# 4HP_555_eg.net
KiCad netlist of a schematic drawn in EAGLE
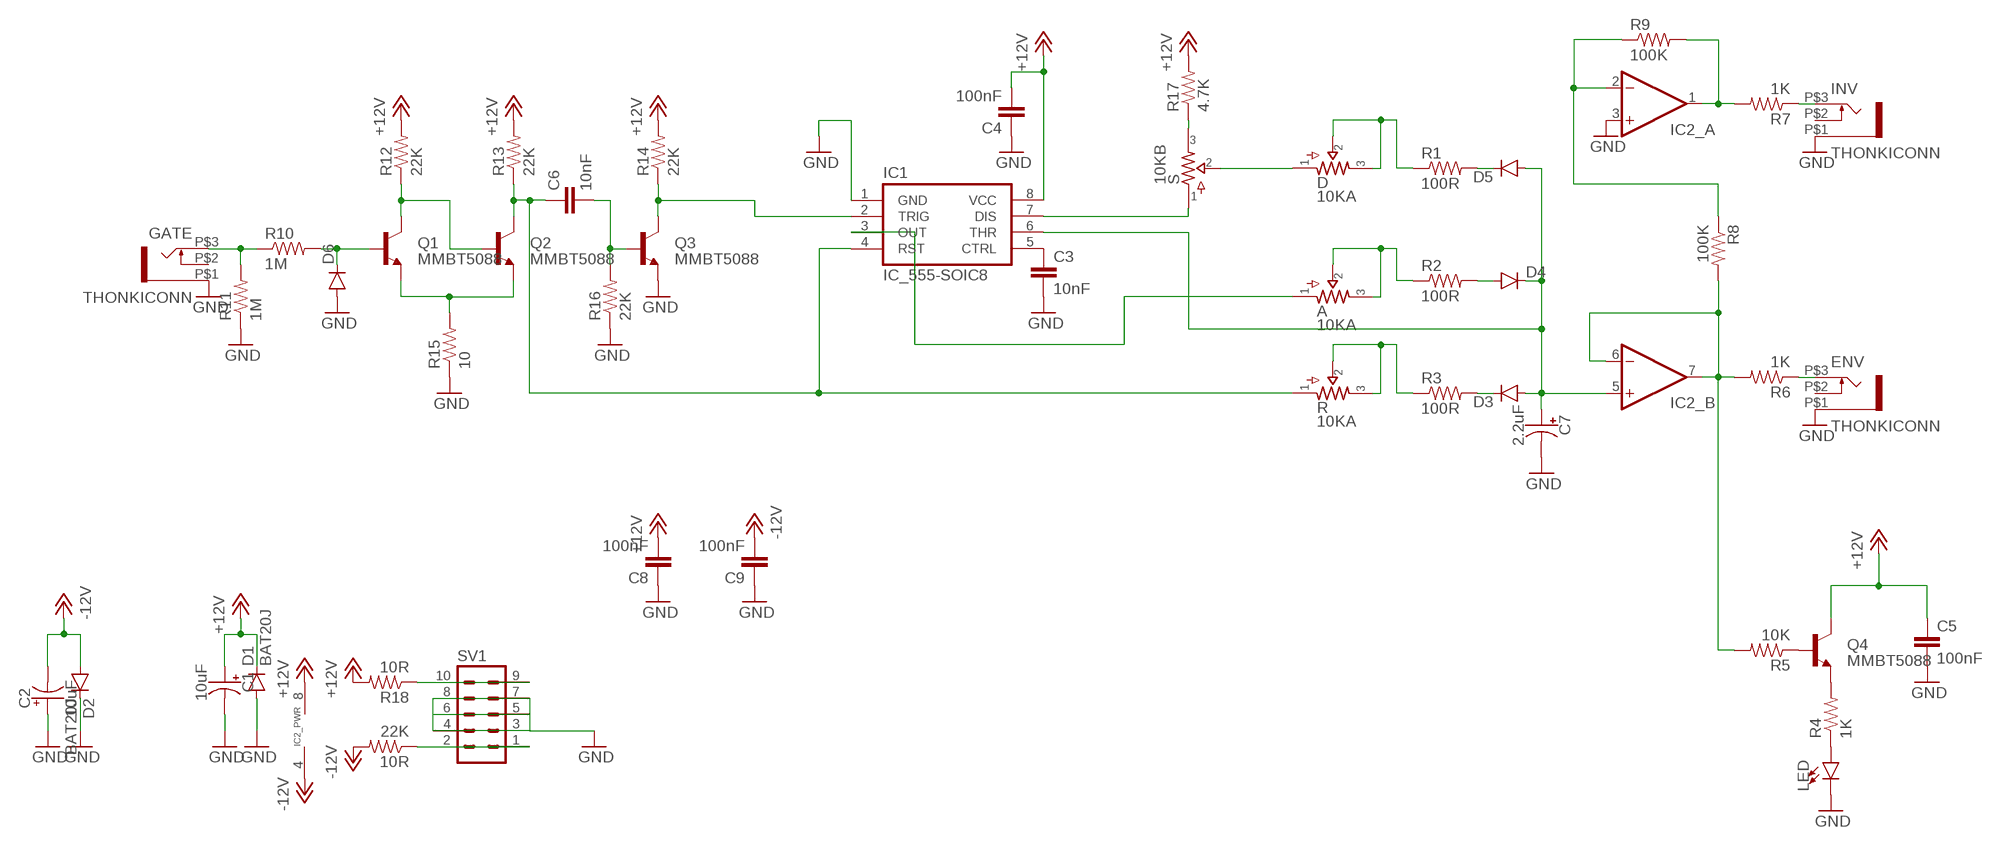
[diagram p0: schematic, sheet 1]

(export (version "E")
  (design (tool "Eeschema 10.0.6"))
  (components
    (comp (ref "10R")
      (value "22K")
      (footprint "eagle-import:0603-RES")
      (libsource (lib "eagle-import") (part "RESISTOR0603-RES"))
    )
    (comp (ref "A")
      (value "10KA")
      (footprint "eagle-import:9MM_W_MOUNTS-2MMHOLES")
      (libsource (lib "eagle-import") (part "POTS9MM_MOUNTED_2MMH"))
    )
    (comp (ref "C1")
      (value "10uF")
      (footprint "eagle-import:050_020_1")
      (libsource (lib "eagle-import") (part "0501"))
    )
    (comp (ref "C2")
      (value "10uF")
      (footprint "eagle-import:050_020_1")
      (libsource (lib "eagle-import") (part "0501"))
    )
    (comp (ref "C3")
      (value "10nF")
      (footprint "eagle-import:0603-CAP")
      (libsource (lib "eagle-import") (part "CAP0603-CAP"))
    )
    (comp (ref "C4")
      (value "100nF")
      (footprint "eagle-import:0603-CAP")
      (libsource (lib "eagle-import") (part "CAP0603-CAP"))
    )
    (comp (ref "C5")
      (value "100nF")
      (footprint "eagle-import:0603-CAP")
      (libsource (lib "eagle-import") (part "CAP0603-CAP"))
    )
    (comp (ref "C6")
      (value "10nF")
      (footprint "eagle-import:0603-CAP")
      (libsource (lib "eagle-import") (part "CAP0603-CAP"))
    )
    (comp (ref "C7")
      (value "2.2uF")
      (footprint "eagle-import:050_020_1")
      (libsource (lib "eagle-import") (part "0501"))
    )
    (comp (ref "C8")
      (value "100nF")
      (footprint "eagle-import:0603-CAP")
      (libsource (lib "eagle-import") (part "CAP0603-CAP"))
    )
    (comp (ref "C9")
      (value "100nF")
      (footprint "eagle-import:0603-CAP")
      (libsource (lib "eagle-import") (part "CAP0603-CAP"))
    )
    (comp (ref "D")
      (value "10KA")
      (footprint "eagle-import:9MM_W_MOUNTS-2MMHOLES")
      (libsource (lib "eagle-import") (part "POTS9MM_MOUNTED_2MMH"))
    )
    (comp (ref "D1")
      (value "BAT20J")
      (footprint "eagle-import:SOD-123")
      (libsource (lib "eagle-import") (part "DIODESOD123"))
    )
    (comp (ref "D2")
      (value "BAT20J")
      (footprint "eagle-import:SOD-123")
      (libsource (lib "eagle-import") (part "DIODESOD123"))
    )
    (comp (ref "D3")
      (value "DIODESOD")
      (footprint "eagle-import:SOD-323")
      (libsource (lib "eagle-import") (part "DIODESOD"))
    )
    (comp (ref "D4")
      (value "DIODESOD")
      (footprint "eagle-import:SOD-323")
      (libsource (lib "eagle-import") (part "DIODESOD"))
    )
    (comp (ref "D5")
      (value "DIODESOD")
      (footprint "eagle-import:SOD-323")
      (libsource (lib "eagle-import") (part "DIODESOD"))
    )
    (comp (ref "D6")
      (value "DIODESOD")
      (footprint "eagle-import:SOD-323")
      (libsource (lib "eagle-import") (part "DIODESOD"))
    )
    (comp (ref "ENV")
      (value "THONKICONN")
      (footprint "eagle-import:THONKICONN")
      (libsource (lib "eagle-import") (part "THONKICONN"))
    )
    (comp (ref "GATE")
      (value "THONKICONN")
      (footprint "eagle-import:THONKICONN")
      (libsource (lib "eagle-import") (part "THONKICONN"))
    )
    (comp (ref "IC1")
      (value "IC_555-SOIC8")
      (footprint "eagle-import:SOIC-8")
      (libsource (lib "eagle-import") (part "IC_555-SOIC8"))
    )
    (comp (ref "IC2")
      (value "DUALSMD")
      (footprint "eagle-import:SO08")
      (libsource (lib "eagle-import") (part "DUALSMD"))
    )
    (comp (ref "INV")
      (value "THONKICONN")
      (footprint "eagle-import:THONKICONN")
      (libsource (lib "eagle-import") (part "THONKICONN"))
    )
    (comp (ref "LED")
      (value "LED5MM")
      (footprint "eagle-import:LED_5MM")
      (libsource (lib "eagle-import") (part "LED5MM"))
    )
    (comp (ref "Q1")
      (value "MMBT5088")
      (footprint "eagle-import:SOT23")
      (libsource (lib "eagle-import") (part "TRANSISTOR_NPNMMBT5088"))
    )
    (comp (ref "Q2")
      (value "MMBT5088")
      (footprint "eagle-import:SOT23")
      (libsource (lib "eagle-import") (part "TRANSISTOR_NPNMMBT5088"))
    )
    (comp (ref "Q3")
      (value "MMBT5088")
      (footprint "eagle-import:SOT23")
      (libsource (lib "eagle-import") (part "TRANSISTOR_NPNMMBT5088"))
    )
    (comp (ref "Q4")
      (value "MMBT5088")
      (footprint "eagle-import:SOT23")
      (libsource (lib "eagle-import") (part "TRANSISTOR_NPNMMBT5088"))
    )
    (comp (ref "R")
      (value "10KA")
      (footprint "eagle-import:9MM_W_MOUNTS-2MMHOLES")
      (libsource (lib "eagle-import") (part "POTS9MM_MOUNTED_2MMH"))
    )
    (comp (ref "R1")
      (value "100R")
      (footprint "eagle-import:0603-RES")
      (libsource (lib "eagle-import") (part "RESISTOR0603-RES"))
    )
    (comp (ref "R2")
      (value "100R")
      (footprint "eagle-import:0603-RES")
      (libsource (lib "eagle-import") (part "RESISTOR0603-RES"))
    )
    (comp (ref "R3")
      (value "100R")
      (footprint "eagle-import:0603-RES")
      (libsource (lib "eagle-import") (part "RESISTOR0603-RES"))
    )
    (comp (ref "R4")
      (value "1K")
      (footprint "eagle-import:0603-RES")
      (libsource (lib "eagle-import") (part "RESISTOR0603-RES"))
    )
    (comp (ref "R5")
      (value "10K")
      (footprint "eagle-import:0603-RES")
      (libsource (lib "eagle-import") (part "RESISTOR0603-RES"))
    )
    (comp (ref "R6")
      (value "1K")
      (footprint "eagle-import:0603-RES")
      (libsource (lib "eagle-import") (part "RESISTOR0603-RES"))
    )
    (comp (ref "R7")
      (value "1K")
      (footprint "eagle-import:0603-RES")
      (libsource (lib "eagle-import") (part "RESISTOR0603-RES"))
    )
    (comp (ref "R8")
      (value "100K")
      (footprint "eagle-import:0603-RES")
      (libsource (lib "eagle-import") (part "RESISTOR0603-RES"))
    )
    (comp (ref "R9")
      (value "100K")
      (footprint "eagle-import:0603-RES")
      (libsource (lib "eagle-import") (part "RESISTOR0603-RES"))
    )
    (comp (ref "R10")
      (value "1M")
      (footprint "eagle-import:0603-RES")
      (libsource (lib "eagle-import") (part "RESISTOR0603-RES"))
    )
    (comp (ref "R11")
      (value "1M")
      (footprint "eagle-import:0603-RES")
      (libsource (lib "eagle-import") (part "RESISTOR0603-RES"))
    )
    (comp (ref "R12")
      (value "22K")
      (footprint "eagle-import:0603-RES")
      (libsource (lib "eagle-import") (part "RESISTOR0603-RES"))
    )
    (comp (ref "R13")
      (value "22K")
      (footprint "eagle-import:0603-RES")
      (libsource (lib "eagle-import") (part "RESISTOR0603-RES"))
    )
    (comp (ref "R14")
      (value "22K")
      (footprint "eagle-import:0603-RES")
      (libsource (lib "eagle-import") (part "RESISTOR0603-RES"))
    )
    (comp (ref "R15")
      (value "10")
      (footprint "eagle-import:0603-RES")
      (libsource (lib "eagle-import") (part "RESISTOR0603-RES"))
    )
    (comp (ref "R16")
      (value "22K")
      (footprint "eagle-import:0603-RES")
      (libsource (lib "eagle-import") (part "RESISTOR0603-RES"))
    )
    (comp (ref "R17")
      (value "4.7K")
      (footprint "eagle-import:0603-RES")
      (libsource (lib "eagle-import") (part "RESISTOR0603-RES"))
    )
    (comp (ref "R18")
      (value "10R")
      (footprint "eagle-import:0603-RES")
      (libsource (lib "eagle-import") (part "RESISTOR0603-RES"))
    )
    (comp (ref "S")
      (value "10KB")
      (footprint "eagle-import:9MM_W_MOUNTS-2MMHOLES")
      (libsource (lib "eagle-import") (part "POTS9MM_MOUNTED_2MMH"))
    )
    (comp (ref "SV1")
      (value "EURO_POWER_HEADER")
      (footprint "eagle-import:EURO_POWER_HEADER")
      (libsource (lib "eagle-import") (part "EURO_POWER_HEADER"))
    )
  )
  (nets
    (net (code "1") (name "+12V") (class "Default")
      (node (ref "C1") (pin "+") (pinfunction "+_+") (pintype "passive"))
      (node (ref "C4") (pin "2") (pinfunction "2_2") (pintype "passive"))
      (node (ref "C5") (pin "1") (pinfunction "1_1") (pintype "passive"))
      (node (ref "C8") (pin "2") (pinfunction "2_2") (pintype "passive"))
      (node (ref "D1") (pin "C") (pinfunction "C_C") (pintype "passive"))
      (node (ref "IC1") (pin "8") (pinfunction "VCC_8") (pintype "power_in"))
      (node (ref "IC2") (pin "8") (pinfunction "V+_8") (pintype "power_in"))
      (node (ref "Q4") (pin "3") (pinfunction "C_3") (pintype "passive"))
      (node (ref "R12") (pin "2") (pinfunction "2_2") (pintype "passive"))
      (node (ref "R13") (pin "2") (pinfunction "2_2") (pintype "passive"))
      (node (ref "R14") (pin "2") (pinfunction "2_2") (pintype "passive"))
      (node (ref "R17") (pin "2") (pinfunction "2_2") (pintype "passive"))
      (node (ref "R18") (pin "2") (pinfunction "2_2") (pintype "passive"))
    )
    (net (code "2") (name "-12V") (class "Default")
      (node (ref "10R") (pin "2") (pinfunction "2_2") (pintype "passive"))
      (node (ref "C2") (pin "-") (pinfunction "-_-") (pintype "passive"))
      (node (ref "C9") (pin "2") (pinfunction "2_2") (pintype "passive"))
      (node (ref "D2") (pin "A") (pinfunction "A_A") (pintype "passive"))
      (node (ref "IC2") (pin "4") (pinfunction "V-_4") (pintype "power_in"))
    )
    (net (code "3") (name "GND") (class "Default")
      (node (ref "C1") (pin "-") (pinfunction "-_-") (pintype "passive"))
      (node (ref "C2") (pin "+") (pinfunction "+_+") (pintype "passive"))
      (node (ref "C3") (pin "2") (pinfunction "2_2") (pintype "passive"))
      (node (ref "C4") (pin "1") (pinfunction "1_1") (pintype "passive"))
      (node (ref "C5") (pin "2") (pinfunction "2_2") (pintype "passive"))
      (node (ref "C7") (pin "-") (pinfunction "-_-") (pintype "passive"))
      (node (ref "C8") (pin "1") (pinfunction "1_1") (pintype "passive"))
      (node (ref "C9") (pin "1") (pinfunction "1_1") (pintype "passive"))
      (node (ref "D1") (pin "A") (pinfunction "A_A") (pintype "passive"))
      (node (ref "D2") (pin "C") (pinfunction "C_C") (pintype "passive"))
      (node (ref "D6") (pin "A") (pinfunction "A_A") (pintype "passive"))
      (node (ref "ENV") (pin "P$1") (pinfunction "5_P$1") (pintype "passive"))
      (node (ref "GATE") (pin "P$1") (pinfunction "5_P$1") (pintype "passive"))
      (node (ref "IC1") (pin "1") (pinfunction "GND_1") (pintype "power_in"))
      (node (ref "IC2") (pin "3") (pinfunction "+IN_3") (pintype "input"))
      (node (ref "INV") (pin "P$1") (pinfunction "5_P$1") (pintype "passive"))
      (node (ref "LED") (pin "K") (pinfunction "C_K") (pintype "passive"))
      (node (ref "Q3") (pin "2") (pinfunction "E_2") (pintype "passive"))
      (node (ref "R11") (pin "1") (pinfunction "1_1") (pintype "passive"))
      (node (ref "R15") (pin "1") (pinfunction "1_1") (pintype "passive"))
      (node (ref "R16") (pin "1") (pinfunction "1_1") (pintype "passive"))
      (node (ref "SV1") (pin "3") (pinfunction "3_3") (pintype "passive"))
      (node (ref "SV1") (pin "4") (pinfunction "4_4") (pintype "passive"))
      (node (ref "SV1") (pin "5") (pinfunction "5_5") (pintype "passive"))
      (node (ref "SV1") (pin "6") (pinfunction "6_6") (pintype "passive"))
      (node (ref "SV1") (pin "7") (pinfunction "7_7") (pintype "passive"))
      (node (ref "SV1") (pin "8") (pinfunction "8_8") (pintype "passive"))
    )
    (net (code "4") (name "Net-(10R-Pad1)") (class "Default")
      (node (ref "10R") (pin "1") (pinfunction "1_1") (pintype "passive"))
      (node (ref "SV1") (pin "1") (pinfunction "1_1") (pintype "passive"))
      (node (ref "SV1") (pin "2") (pinfunction "2_2") (pintype "passive"))
    )
    (net (code "5") (name "Net-(A-1)") (class "Default")
      (node (ref "A") (pin "P$1") (pinfunction "1_P$1") (pintype "passive"))
      (node (ref "IC1") (pin "3") (pinfunction "OUT_3") (pintype "output"))
    )
    (net (code "6") (name "Net-(A-2)") (class "Default")
      (node (ref "A") (pin "P$2") (pinfunction "2_P$2") (pintype "passive"))
      (node (ref "A") (pin "P$3") (pinfunction "3_P$3") (pintype "passive"))
      (node (ref "R2") (pin "1") (pinfunction "1_1") (pintype "passive"))
    )
    (net (code "7") (name "Net-(D-1)") (class "Default")
      (node (ref "D") (pin "P$1") (pinfunction "1_P$1") (pintype "passive"))
      (node (ref "S") (pin "P$2") (pinfunction "2_P$2") (pintype "passive"))
    )
    (net (code "8") (name "Net-(D-2)") (class "Default")
      (node (ref "D") (pin "P$2") (pinfunction "2_P$2") (pintype "passive"))
      (node (ref "D") (pin "P$3") (pinfunction "3_P$3") (pintype "passive"))
      (node (ref "R1") (pin "1") (pinfunction "1_1") (pintype "passive"))
    )
    (net (code "9") (name "Net-(D3-PadC)") (class "Default")
      (node (ref "D3") (pin "C") (pinfunction "C_C") (pintype "passive"))
      (node (ref "R3") (pin "2") (pinfunction "2_2") (pintype "passive"))
    )
    (net (code "10") (name "Net-(D4-PadA)") (class "Default")
      (node (ref "D4") (pin "A") (pinfunction "A_A") (pintype "passive"))
      (node (ref "R2") (pin "2") (pinfunction "2_2") (pintype "passive"))
    )
    (net (code "11") (name "Net-(D5-PadC)") (class "Default")
      (node (ref "D5") (pin "C") (pinfunction "C_C") (pintype "passive"))
      (node (ref "R1") (pin "2") (pinfunction "2_2") (pintype "passive"))
    )
    (net (code "12") (name "Net-(ENV-3)") (class "Default")
      (node (ref "ENV") (pin "P$3") (pinfunction "3_P$3") (pintype "passive"))
      (node (ref "R6") (pin "1") (pinfunction "1_1") (pintype "passive"))
    )
    (net (code "13") (name "Net-(GATE-3)") (class "Default")
      (node (ref "GATE") (pin "P$3") (pinfunction "3_P$3") (pintype "passive"))
      (node (ref "R10") (pin "1") (pinfunction "1_1") (pintype "passive"))
      (node (ref "R11") (pin "2") (pinfunction "2_2") (pintype "passive"))
    )
    (net (code "14") (name "Net-(IC1-CTRL)") (class "Default")
      (node (ref "C3") (pin "1") (pinfunction "1_1") (pintype "passive"))
      (node (ref "IC1") (pin "5") (pinfunction "CTRL_5") (pintype "power_in"))
    )
    (net (code "15") (name "Net-(IC1-DIS)") (class "Default")
      (node (ref "IC1") (pin "7") (pinfunction "DIS_7") (pintype "input"))
      (node (ref "S") (pin "P$1") (pinfunction "1_P$1") (pintype "passive"))
    )
    (net (code "16") (name "Net-(IC1-RST)") (class "Default")
      (node (ref "C6") (pin "1") (pinfunction "1_1") (pintype "passive"))
      (node (ref "IC1") (pin "4") (pinfunction "RST_4") (pintype "input"))
      (node (ref "Q2") (pin "3") (pinfunction "C_3") (pintype "passive"))
      (node (ref "R") (pin "P$1") (pinfunction "1_P$1") (pintype "passive"))
      (node (ref "R13") (pin "1") (pinfunction "1_1") (pintype "passive"))
    )
    (net (code "17") (name "Net-(IC1-THR)") (class "Default")
      (node (ref "C7") (pin "+") (pinfunction "+_+") (pintype "passive"))
      (node (ref "D3") (pin "A") (pinfunction "A_A") (pintype "passive"))
      (node (ref "D4") (pin "C") (pinfunction "C_C") (pintype "passive"))
      (node (ref "D5") (pin "A") (pinfunction "A_A") (pintype "passive"))
      (node (ref "IC1") (pin "6") (pinfunction "THR_6") (pintype "input"))
      (node (ref "IC2") (pin "5") (pinfunction "+IN_5") (pintype "input"))
    )
    (net (code "18") (name "Net-(IC1-TRIG)") (class "Default")
      (node (ref "IC1") (pin "2") (pinfunction "TRIG_2") (pintype "input"))
      (node (ref "Q3") (pin "3") (pinfunction "C_3") (pintype "passive"))
      (node (ref "R14") (pin "1") (pinfunction "1_1") (pintype "passive"))
    )
    (net (code "19") (name "Net-(IC2A--IN)") (class "Default")
      (node (ref "IC2") (pin "2") (pinfunction "-IN_2") (pintype "input"))
      (node (ref "R8") (pin "1") (pinfunction "1_1") (pintype "passive"))
      (node (ref "R9") (pin "1") (pinfunction "1_1") (pintype "passive"))
    )
    (net (code "20") (name "Net-(IC2A-OUT)") (class "Default")
      (node (ref "IC2") (pin "1") (pinfunction "OUT_1") (pintype "output"))
      (node (ref "R7") (pin "2") (pinfunction "2_2") (pintype "passive"))
      (node (ref "R9") (pin "2") (pinfunction "2_2") (pintype "passive"))
    )
    (net (code "21") (name "Net-(IC2B--IN)") (class "Default")
      (node (ref "IC2") (pin "6") (pinfunction "-IN_6") (pintype "input"))
      (node (ref "IC2") (pin "7") (pinfunction "OUT_7") (pintype "output"))
      (node (ref "R5") (pin "2") (pinfunction "2_2") (pintype "passive"))
      (node (ref "R6") (pin "2") (pinfunction "2_2") (pintype "passive"))
      (node (ref "R8") (pin "2") (pinfunction "2_2") (pintype "passive"))
    )
    (net (code "22") (name "Net-(INV-3)") (class "Default")
      (node (ref "INV") (pin "P$3") (pinfunction "3_P$3") (pintype "passive"))
      (node (ref "R7") (pin "1") (pinfunction "1_1") (pintype "passive"))
    )
    (net (code "23") (name "Net-(LED-PadA)") (class "Default")
      (node (ref "LED") (pin "A") (pinfunction "A_A") (pintype "passive"))
      (node (ref "R4") (pin "1") (pinfunction "1_1") (pintype "passive"))
    )
    (net (code "24") (name "Net-(Q1-B)") (class "Default")
      (node (ref "D6") (pin "C") (pinfunction "C_C") (pintype "passive"))
      (node (ref "Q1") (pin "1") (pinfunction "B_1") (pintype "passive"))
      (node (ref "R10") (pin "2") (pinfunction "2_2") (pintype "passive"))
    )
    (net (code "25") (name "Net-(Q1-C)") (class "Default")
      (node (ref "Q1") (pin "3") (pinfunction "C_3") (pintype "passive"))
      (node (ref "Q2") (pin "1") (pinfunction "B_1") (pintype "passive"))
      (node (ref "R12") (pin "1") (pinfunction "1_1") (pintype "passive"))
    )
    (net (code "26") (name "Net-(Q1-E)") (class "Default")
      (node (ref "Q1") (pin "2") (pinfunction "E_2") (pintype "passive"))
      (node (ref "Q2") (pin "2") (pinfunction "E_2") (pintype "passive"))
      (node (ref "R15") (pin "2") (pinfunction "2_2") (pintype "passive"))
    )
    (net (code "27") (name "Net-(Q3-B)") (class "Default")
      (node (ref "C6") (pin "2") (pinfunction "2_2") (pintype "passive"))
      (node (ref "Q3") (pin "1") (pinfunction "B_1") (pintype "passive"))
      (node (ref "R16") (pin "2") (pinfunction "2_2") (pintype "passive"))
    )
    (net (code "28") (name "Net-(Q4-B)") (class "Default")
      (node (ref "Q4") (pin "1") (pinfunction "B_1") (pintype "passive"))
      (node (ref "R5") (pin "1") (pinfunction "1_1") (pintype "passive"))
    )
    (net (code "29") (name "Net-(Q4-E)") (class "Default")
      (node (ref "Q4") (pin "2") (pinfunction "E_2") (pintype "passive"))
      (node (ref "R4") (pin "2") (pinfunction "2_2") (pintype "passive"))
    )
    (net (code "30") (name "Net-(R-2)") (class "Default")
      (node (ref "R") (pin "P$2") (pinfunction "2_P$2") (pintype "passive"))
      (node (ref "R") (pin "P$3") (pinfunction "3_P$3") (pintype "passive"))
      (node (ref "R3") (pin "1") (pinfunction "1_1") (pintype "passive"))
    )
    (net (code "31") (name "Net-(R18-Pad1)") (class "Default")
      (node (ref "R18") (pin "1") (pinfunction "1_1") (pintype "passive"))
      (node (ref "SV1") (pin "10") (pinfunction "10_10") (pintype "passive"))
      (node (ref "SV1") (pin "9") (pinfunction "9_9") (pintype "passive"))
    )
    (net (code "32") (name "Net-(S-3)") (class "Default")
      (node (ref "R17") (pin "1") (pinfunction "1_1") (pintype "passive"))
      (node (ref "S") (pin "P$3") (pinfunction "3_P$3") (pintype "passive"))
    )
    (net (code "33") (name "unconnected-(ENV-4-PadP$2)") (class "Default")
      (node (ref "ENV") (pin "P$2") (pinfunction "4_P$2") (pintype "passive"))
    )
    (net (code "34") (name "unconnected-(GATE-4-PadP$2)") (class "Default")
      (node (ref "GATE") (pin "P$2") (pinfunction "4_P$2") (pintype "passive"))
    )
    (net (code "35") (name "unconnected-(INV-4-PadP$2)") (class "Default")
      (node (ref "INV") (pin "P$2") (pinfunction "4_P$2") (pintype "passive"))
    )
  )
)
